# c200.net
KiCad netlist of a schematic drawn in EAGLE
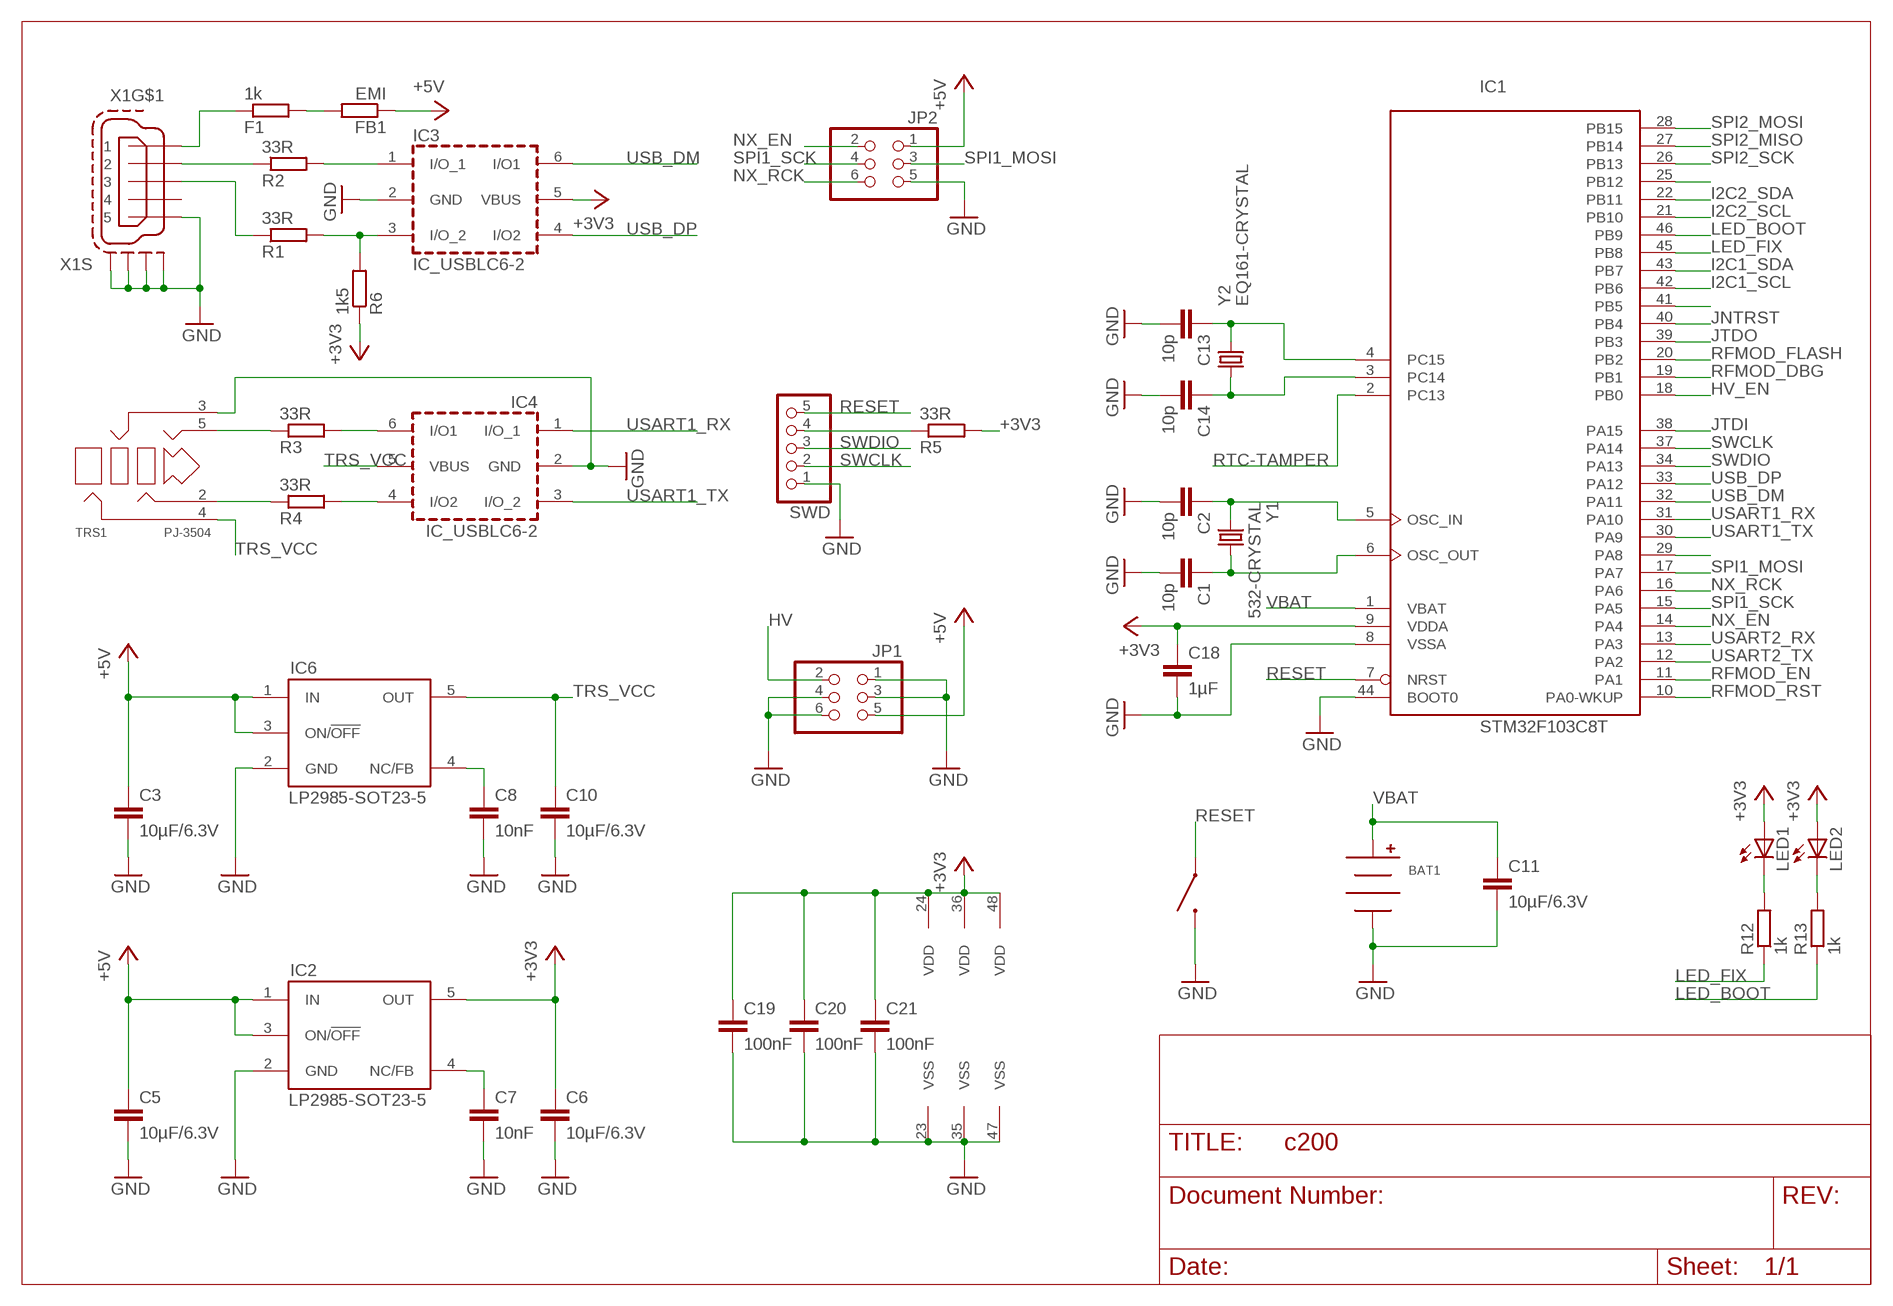
[diagram p0: schematic, sheet 1, part 1 of 2]
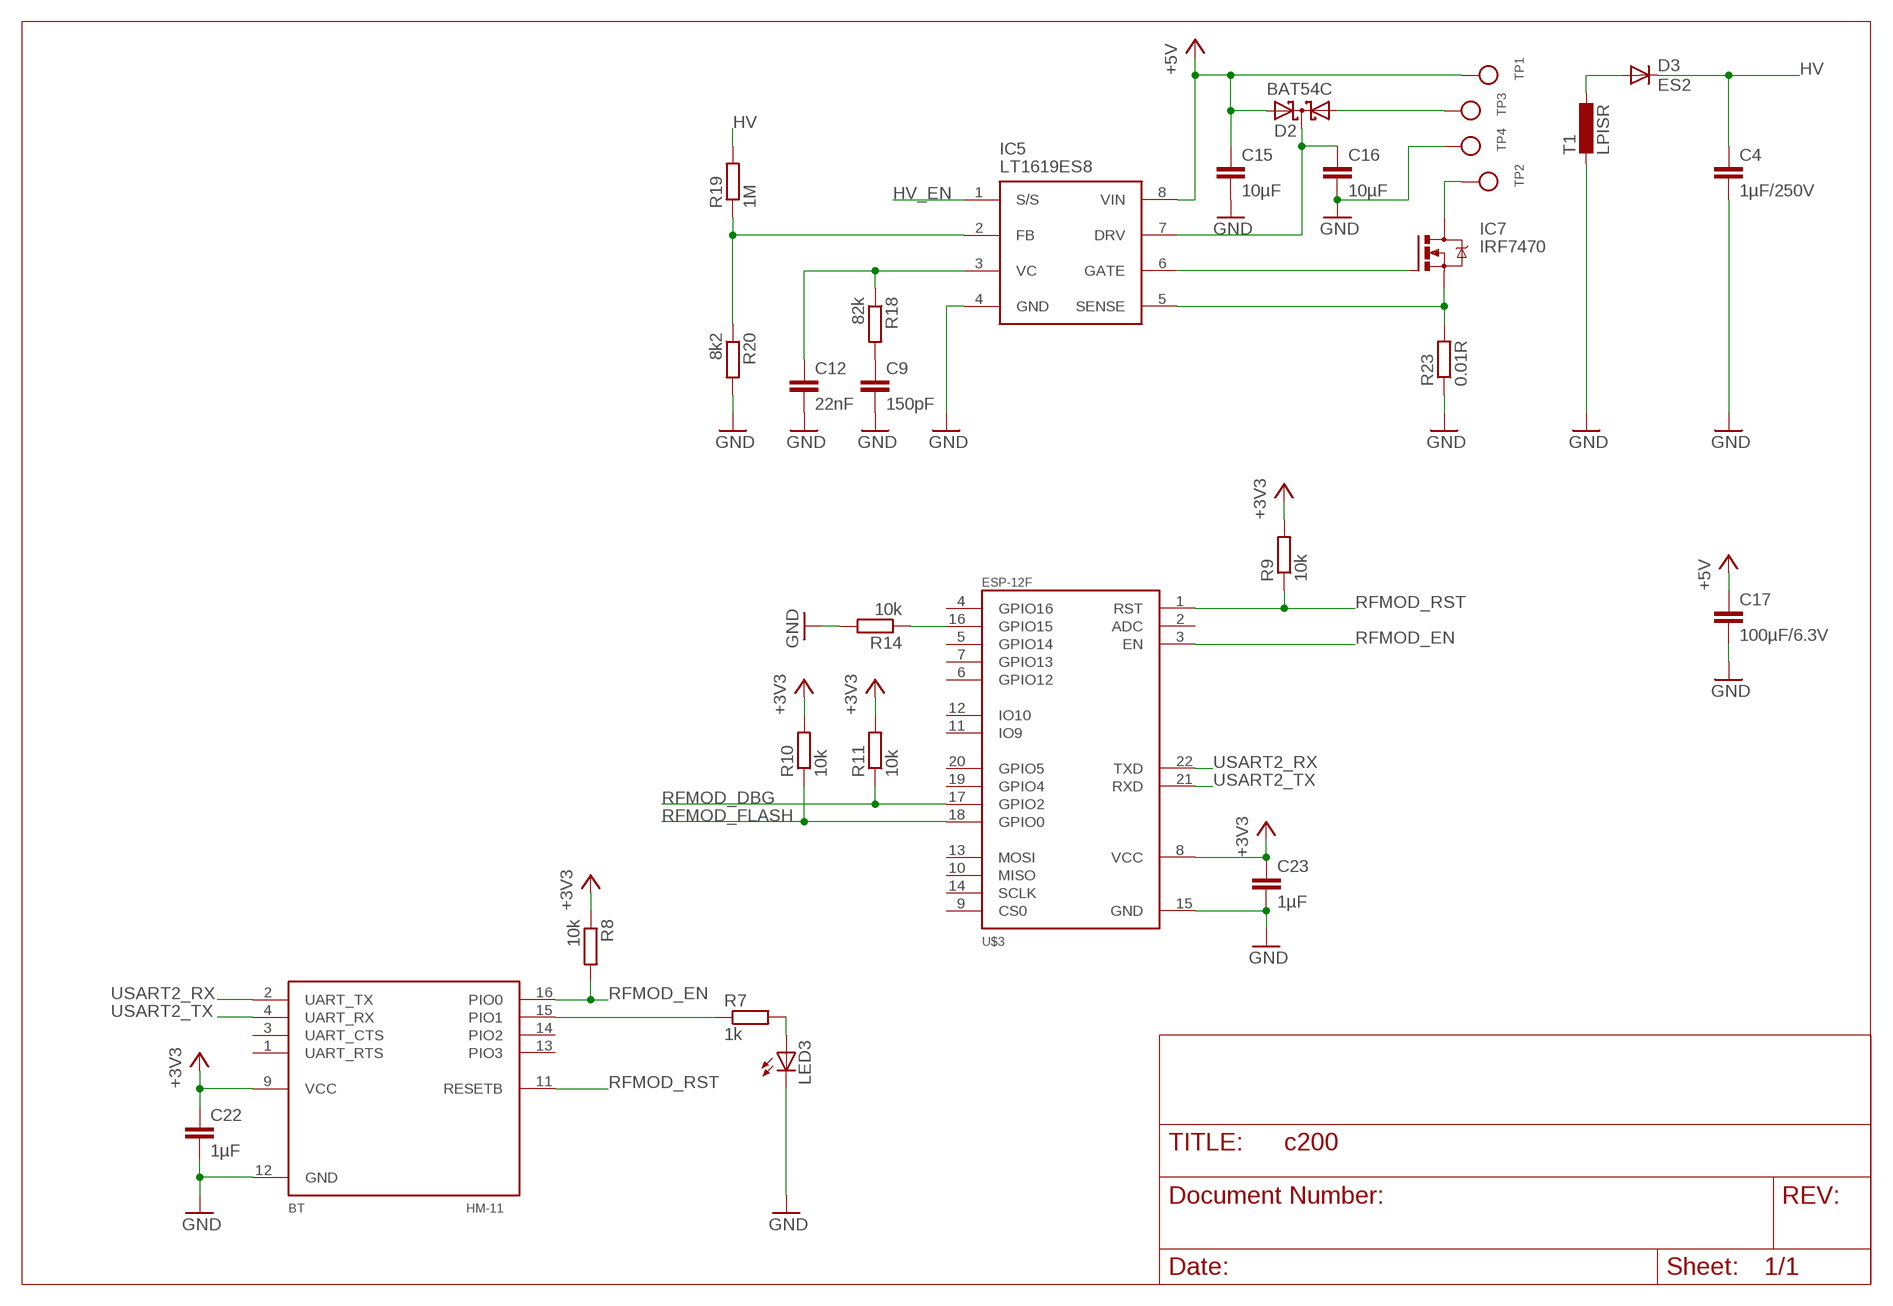
[diagram p1: schematic, sheet 1, part 2 of 2]

(export (version "E")
  (design (tool "Eeschema 10.0.6"))
  (components
    (comp (ref "BAT1")
      (value "CR1220-HOLDER")
      (footprint "eagle-import:HARWIN-CR1220")
      (libsource (lib "eagle-import") (part "CR1220-HOLDER"))
    )
    (comp (ref "BT")
      (value "HM-11")
      (footprint "eagle-import:HM-11")
      (libsource (lib "eagle-import") (part "HM-11"))
    )
    (comp (ref "C1")
      (value "10p")
      (footprint "eagle-import:C0603")
      (libsource (lib "eagle-import") (part "C-EUC0603"))
    )
    (comp (ref "C2")
      (value "10p")
      (footprint "eagle-import:C0603")
      (libsource (lib "eagle-import") (part "C-EUC0603"))
    )
    (comp (ref "C3")
      (value "10µF/6.3V")
      (footprint "eagle-import:C0603")
      (libsource (lib "eagle-import") (part "C-EUC0603"))
    )
    (comp (ref "C4")
      (value "1µF/250V")
      (footprint "eagle-import:C2220K")
      (libsource (lib "eagle-import") (part "C-EUC2220K"))
    )
    (comp (ref "C5")
      (value "10µF/6.3V")
      (footprint "eagle-import:C0603")
      (libsource (lib "eagle-import") (part "C-EUC0603"))
    )
    (comp (ref "C6")
      (value "10µF/6.3V")
      (footprint "eagle-import:C0603")
      (libsource (lib "eagle-import") (part "C-EUC0603"))
    )
    (comp (ref "C7")
      (value "10nF")
      (footprint "eagle-import:C0603")
      (libsource (lib "eagle-import") (part "C-EUC0603"))
    )
    (comp (ref "C8")
      (value "10nF")
      (footprint "eagle-import:C0603")
      (libsource (lib "eagle-import") (part "C-EUC0603"))
    )
    (comp (ref "C9")
      (value "150pF")
      (footprint "eagle-import:C0603")
      (libsource (lib "eagle-import") (part "C-EUC0603"))
    )
    (comp (ref "C10")
      (value "10µF/6.3V")
      (footprint "eagle-import:C0603")
      (libsource (lib "eagle-import") (part "C-EUC0603"))
    )
    (comp (ref "C11")
      (value "10µF/6.3V")
      (footprint "eagle-import:C0603")
      (libsource (lib "eagle-import") (part "C-EUC0603"))
    )
    (comp (ref "C12")
      (value "22nF")
      (footprint "eagle-import:C0603")
      (libsource (lib "eagle-import") (part "C-EUC0603"))
    )
    (comp (ref "C13")
      (value "10p")
      (footprint "eagle-import:C0603")
      (libsource (lib "eagle-import") (part "C-EUC0603"))
    )
    (comp (ref "C14")
      (value "10p")
      (footprint "eagle-import:C0603")
      (libsource (lib "eagle-import") (part "C-EUC0603"))
    )
    (comp (ref "C15")
      (value "10µF")
      (footprint "eagle-import:C0603")
      (libsource (lib "eagle-import") (part "C-EUC0603"))
    )
    (comp (ref "C16")
      (value "10µF")
      (footprint "eagle-import:C0603")
      (libsource (lib "eagle-import") (part "C-EUC0603"))
    )
    (comp (ref "C17")
      (value "100µF/6.3V")
      (footprint "eagle-import:C1210")
      (libsource (lib "eagle-import") (part "C-EUC1210"))
    )
    (comp (ref "C18")
      (value "1µF")
      (footprint "eagle-import:C0603")
      (libsource (lib "eagle-import") (part "C-EUC0603"))
    )
    (comp (ref "C19")
      (value "100nF")
      (footprint "eagle-import:C0603")
      (libsource (lib "eagle-import") (part "C-EUC0603"))
    )
    (comp (ref "C20")
      (value "100nF")
      (footprint "eagle-import:C0603")
      (libsource (lib "eagle-import") (part "C-EUC0603"))
    )
    (comp (ref "C21")
      (value "100nF")
      (footprint "eagle-import:C0603")
      (libsource (lib "eagle-import") (part "C-EUC0603"))
    )
    (comp (ref "C22")
      (value "1µF")
      (footprint "eagle-import:C0603")
      (libsource (lib "eagle-import") (part "C-EUC0603"))
    )
    (comp (ref "C23")
      (value "1µF")
      (footprint "eagle-import:C0603")
      (libsource (lib "eagle-import") (part "C-EUC0603"))
    )
    (comp (ref "D2")
      (value "BAT54C")
      (footprint "eagle-import:SOT23")
      (libsource (lib "eagle-import") (part "BAT54C"))
    )
    (comp (ref "D3")
      (value "ES2")
      (footprint "eagle-import:DO-214AA")
      (libsource (lib "eagle-import") (part "ES2"))
    )
    (comp (ref "F1")
      (value "1k")
      (footprint "eagle-import:R0603")
      (libsource (lib "eagle-import") (part "R-EU_R0603"))
    )
    (comp (ref "FB1")
      (value "EMI")
      (footprint "eagle-import:R0603")
      (libsource (lib "eagle-import") (part "R-EU_R0603"))
    )
    (comp (ref "IC1")
      (value "STM32F103C8T")
      (footprint "eagle-import:LQFP48")
      (libsource (lib "eagle-import") (part "STM32F103CT8"))
    )
    (comp (ref "IC2")
      (value "LP2985-SOT23-5")
      (footprint "eagle-import:SOT23-5")
      (libsource (lib "eagle-import") (part "LP2985-SOT23-5"))
    )
    (comp (ref "IC3")
      (value "IC_USBLC6-2")
      (footprint "eagle-import:SOT-23-6L")
      (libsource (lib "eagle-import") (part "IC_USBLC6-2"))
    )
    (comp (ref "IC4")
      (value "IC_USBLC6-2")
      (footprint "eagle-import:SOT-23-6L")
      (libsource (lib "eagle-import") (part "IC_USBLC6-2"))
    )
    (comp (ref "IC5")
      (value "LT1619ES8")
      (footprint "eagle-import:SO8")
      (libsource (lib "eagle-import") (part "LT1619ES8"))
    )
    (comp (ref "IC6")
      (value "LP2985-SOT23-5")
      (footprint "eagle-import:SOT23-5")
      (libsource (lib "eagle-import") (part "LP2985-SOT23-5"))
    )
    (comp (ref "IC7")
      (value "IRF7470")
      (footprint "eagle-import:SO8")
      (libsource (lib "eagle-import") (part "IRF7470"))
    )
    (comp (ref "ISP")
      (value "TACT-SWITCH-40-40")
      (footprint "eagle-import:40-40")
      (libsource (lib "eagle-import") (part "TACT-SWITCH-40-40"))
    )
    (comp (ref "JP1")
      (value "PINHD-2X3_2.54-SMD")
      (footprint "eagle-import:2X03SMD")
      (libsource (lib "eagle-import") (part "PINHD-2X3_2.54-SMD"))
    )
    (comp (ref "JP2")
      (value "PINHD-2X3_2.54-SMD")
      (footprint "eagle-import:2X03SMD")
      (libsource (lib "eagle-import") (part "PINHD-2X3_2.54-SMD"))
    )
    (comp (ref "LED1")
      (value "LEDCHIP-LED0603")
      (footprint "eagle-import:CHIP-LED0603")
      (libsource (lib "eagle-import") (part "LEDCHIP-LED0603"))
    )
    (comp (ref "LED2")
      (value "LEDCHIP-LED0603")
      (footprint "eagle-import:CHIP-LED0603")
      (libsource (lib "eagle-import") (part "LEDCHIP-LED0603"))
    )
    (comp (ref "LED3")
      (value "LEDCHIP-LED0603")
      (footprint "eagle-import:CHIP-LED0603")
      (libsource (lib "eagle-import") (part "LEDCHIP-LED0603"))
    )
    (comp (ref "R1")
      (value "33R")
      (footprint "eagle-import:R0603")
      (libsource (lib "eagle-import") (part "R-EU_R0603"))
    )
    (comp (ref "R2")
      (value "33R")
      (footprint "eagle-import:R0603")
      (libsource (lib "eagle-import") (part "R-EU_R0603"))
    )
    (comp (ref "R3")
      (value "33R")
      (footprint "eagle-import:R0603")
      (libsource (lib "eagle-import") (part "R-EU_R0603"))
    )
    (comp (ref "R4")
      (value "33R")
      (footprint "eagle-import:R0603")
      (libsource (lib "eagle-import") (part "R-EU_R0603"))
    )
    (comp (ref "R5")
      (value "33R")
      (footprint "eagle-import:R0603")
      (libsource (lib "eagle-import") (part "R-EU_R0603"))
    )
    (comp (ref "R6")
      (value "1k5")
      (footprint "eagle-import:R0603")
      (libsource (lib "eagle-import") (part "R-EU_R0603"))
    )
    (comp (ref "R7")
      (value "1k")
      (footprint "eagle-import:R0603")
      (libsource (lib "eagle-import") (part "R-EU_R0603"))
    )
    (comp (ref "R8")
      (value "10k")
      (footprint "eagle-import:R0603")
      (libsource (lib "eagle-import") (part "R-EU_R0603"))
    )
    (comp (ref "R9")
      (value "10k")
      (footprint "eagle-import:R0603")
      (libsource (lib "eagle-import") (part "R-EU_R0603"))
    )
    (comp (ref "R10")
      (value "10k")
      (footprint "eagle-import:R0603")
      (libsource (lib "eagle-import") (part "R-EU_R0603"))
    )
    (comp (ref "R11")
      (value "10k")
      (footprint "eagle-import:R0603")
      (libsource (lib "eagle-import") (part "R-EU_R0603"))
    )
    (comp (ref "R12")
      (value "1k")
      (footprint "eagle-import:R0603")
      (libsource (lib "eagle-import") (part "R-EU_R0603"))
    )
    (comp (ref "R13")
      (value "1k")
      (footprint "eagle-import:R0603")
      (libsource (lib "eagle-import") (part "R-EU_R0603"))
    )
    (comp (ref "R14")
      (value "10k")
      (footprint "eagle-import:R0603")
      (libsource (lib "eagle-import") (part "R-EU_R0603"))
    )
    (comp (ref "R18")
      (value "82k")
      (footprint "eagle-import:R0603")
      (libsource (lib "eagle-import") (part "R-EU_R0603"))
    )
    (comp (ref "R19")
      (value "1M")
      (footprint "eagle-import:M1206")
      (libsource (lib "eagle-import") (part "R-EU_M1206"))
    )
    (comp (ref "R20")
      (value "8k2")
      (footprint "eagle-import:R0603")
      (libsource (lib "eagle-import") (part "R-EU_R0603"))
    )
    (comp (ref "R23")
      (value "0.01R")
      (footprint "eagle-import:R1206")
      (libsource (lib "eagle-import") (part "R-EU_R1206"))
    )
    (comp (ref "SWD")
      (value "HEADER-1X5ROUND")
      (footprint "eagle-import:1X05_ROUND")
      (libsource (lib "eagle-import") (part "HEADER-1X5ROUND"))
    )
    (comp (ref "T1")
      (value "LPISR")
      (footprint "eagle-import:PISR")
      (libsource (lib "eagle-import") (part "LPISR"))
    )
    (comp (ref "TP1")
      (value "TESTPOINTROUND2MM")
      (footprint "eagle-import:TESTPOINT_ROUND_2MM")
      (libsource (lib "eagle-import") (part "TESTPOINTROUND2MM"))
    )
    (comp (ref "TP2")
      (value "TESTPOINTROUND2MM")
      (footprint "eagle-import:TESTPOINT_ROUND_2MM")
      (libsource (lib "eagle-import") (part "TESTPOINTROUND2MM"))
    )
    (comp (ref "TP3")
      (value "TESTPOINTROUND2MM")
      (footprint "eagle-import:TESTPOINT_ROUND_2MM")
      (libsource (lib "eagle-import") (part "TESTPOINTROUND2MM"))
    )
    (comp (ref "TP4")
      (value "TESTPOINTROUND2MM")
      (footprint "eagle-import:TESTPOINT_ROUND_2MM")
      (libsource (lib "eagle-import") (part "TESTPOINTROUND2MM"))
    )
    (comp (ref "TRS1")
      (value "PJ-3504")
      (footprint "eagle-import:YD-PJ-3504")
      (libsource (lib "eagle-import") (part "PJ-3504"))
    )
    (comp (ref "U$3")
      (value "ESP-12F")
      (footprint "eagle-import:ESP-12F")
      (libsource (lib "eagle-import") (part "ESP-12F"))
    )
    (comp (ref "X1")
      (value "MINI-USB-SCHIELD-32005-201")
      (footprint "eagle-import:32005-201")
      (libsource (lib "eagle-import") (part "MINI-USB-SCHIELD-32005-201"))
    )
    (comp (ref "Y1")
      (value "532-CRYSTAL")
      (footprint "eagle-import:2PIN50X32")
      (libsource (lib "eagle-import") (part "532-CRYSTAL"))
    )
    (comp (ref "Y2")
      (value "EQ161-CRYSTAL")
      (footprint "eagle-import:EQ161")
      (libsource (lib "eagle-import") (part "EQ161-CRYSTAL"))
    )
  )
  (nets
    (net (code "1") (name "+3V3") (class "Default")
      (node (ref "BT") (pin "9") (pinfunction "VCC_9") (pintype "bidirectional"))
      (node (ref "C18") (pin "1") (pinfunction "1_1") (pintype "passive"))
      (node (ref "C19") (pin "1") (pinfunction "1_1") (pintype "passive"))
      (node (ref "C20") (pin "1") (pinfunction "1_1") (pintype "passive"))
      (node (ref "C21") (pin "1") (pinfunction "1_1") (pintype "passive"))
      (node (ref "C22") (pin "1") (pinfunction "1_1") (pintype "passive"))
      (node (ref "C23") (pin "1") (pinfunction "1_1") (pintype "passive"))
      (node (ref "C6") (pin "1") (pinfunction "1_1") (pintype "passive"))
      (node (ref "IC1") (pin "24") (pinfunction "VDD_24") (pintype "power_in"))
      (node (ref "IC1") (pin "36") (pinfunction "VDD_36") (pintype "power_in"))
      (node (ref "IC1") (pin "48") (pinfunction "VDD_48") (pintype "power_in"))
      (node (ref "IC1") (pin "9") (pinfunction "VDDA_9") (pintype "power_in"))
      (node (ref "IC2") (pin "5") (pinfunction "OUT_5") (pintype "bidirectional"))
      (node (ref "IC3") (pin "5") (pinfunction "VBUS_5") (pintype "bidirectional"))
      (node (ref "LED1") (pin "A") (pinfunction "A_A") (pintype "passive"))
      (node (ref "LED2") (pin "A") (pinfunction "A_A") (pintype "passive"))
      (node (ref "R10") (pin "2") (pinfunction "2_2") (pintype "passive"))
      (node (ref "R11") (pin "2") (pinfunction "2_2") (pintype "passive"))
      (node (ref "R5") (pin "2") (pinfunction "2_2") (pintype "passive"))
      (node (ref "R6") (pin "1") (pinfunction "1_1") (pintype "passive"))
      (node (ref "R8") (pin "1") (pinfunction "1_1") (pintype "passive"))
      (node (ref "R9") (pin "2") (pinfunction "2_2") (pintype "passive"))
      (node (ref "U$3") (pin "8") (pinfunction "VCC_8") (pintype "bidirectional"))
    )
    (net (code "2") (name "+5V") (class "Default")
      (node (ref "C15") (pin "1") (pinfunction "1_1") (pintype "passive"))
      (node (ref "C17") (pin "1") (pinfunction "1_1") (pintype "passive"))
      (node (ref "C3") (pin "1") (pinfunction "1_1") (pintype "passive"))
      (node (ref "C5") (pin "1") (pinfunction "1_1") (pintype "passive"))
      (node (ref "D2") (pin "2") (pinfunction "A2_2") (pintype "passive"))
      (node (ref "FB1") (pin "1") (pinfunction "1_1") (pintype "passive"))
      (node (ref "IC2") (pin "1") (pinfunction "IN_1") (pintype "bidirectional"))
      (node (ref "IC2") (pin "3") (pinfunction "ON/~{OFF}_3") (pintype "bidirectional"))
      (node (ref "IC5") (pin "8") (pinfunction "VIN_8") (pintype "bidirectional"))
      (node (ref "IC6") (pin "1") (pinfunction "IN_1") (pintype "bidirectional"))
      (node (ref "IC6") (pin "3") (pinfunction "ON/~{OFF}_3") (pintype "bidirectional"))
      (node (ref "JP1") (pin "5") (pinfunction "5_5") (pintype "passive"))
      (node (ref "JP2") (pin "1") (pinfunction "1_1") (pintype "passive"))
      (node (ref "TP1") (pin "P$1") (pinfunction "P$1_P$1") (pintype "bidirectional"))
    )
    (net (code "3") (name "/HV") (class "Default")
      (node (ref "C4") (pin "1") (pinfunction "1_1") (pintype "passive"))
      (node (ref "D3") (pin "C") (pinfunction "C_C") (pintype "passive"))
      (node (ref "JP1") (pin "2") (pinfunction "2_2") (pintype "passive"))
      (node (ref "R19") (pin "2") (pinfunction "2_2") (pintype "passive"))
    )
    (net (code "4") (name "/HV_EN") (class "Default")
      (node (ref "IC1") (pin "18") (pinfunction "PB0_18") (pintype "bidirectional"))
      (node (ref "IC5") (pin "1") (pinfunction "S/S_1") (pintype "bidirectional"))
    )
    (net (code "5") (name "/I2C1_SCL") (class "Default")
      (node (ref "IC1") (pin "42") (pinfunction "PB6_42") (pintype "bidirectional"))
    )
    (net (code "6") (name "/I2C1_SDA") (class "Default")
      (node (ref "IC1") (pin "43") (pinfunction "PB7_43") (pintype "bidirectional"))
    )
    (net (code "7") (name "/I2C2_SCL") (class "Default")
      (node (ref "IC1") (pin "21") (pinfunction "PB10_21") (pintype "bidirectional"))
    )
    (net (code "8") (name "/I2C2_SDA") (class "Default")
      (node (ref "IC1") (pin "22") (pinfunction "PB11_22") (pintype "bidirectional"))
    )
    (net (code "9") (name "/JNTRST") (class "Default")
      (node (ref "IC1") (pin "40") (pinfunction "PB4_40") (pintype "bidirectional"))
    )
    (net (code "10") (name "/JTDI") (class "Default")
      (node (ref "IC1") (pin "38") (pinfunction "PA15_38") (pintype "bidirectional"))
    )
    (net (code "11") (name "/JTDO") (class "Default")
      (node (ref "IC1") (pin "39") (pinfunction "PB3_39") (pintype "bidirectional"))
    )
    (net (code "12") (name "/LED_BOOT") (class "Default")
      (node (ref "IC1") (pin "46") (pinfunction "PB9_46") (pintype "bidirectional"))
      (node (ref "R13") (pin "1") (pinfunction "1_1") (pintype "passive"))
    )
    (net (code "13") (name "/LED_FIX") (class "Default")
      (node (ref "IC1") (pin "45") (pinfunction "PB8_45") (pintype "bidirectional"))
      (node (ref "R12") (pin "1") (pinfunction "1_1") (pintype "passive"))
    )
    (net (code "14") (name "/NX_EN") (class "Default")
      (node (ref "IC1") (pin "14") (pinfunction "PA4_14") (pintype "bidirectional"))
      (node (ref "JP2") (pin "2") (pinfunction "2_2") (pintype "passive"))
    )
    (net (code "15") (name "/NX_RCK") (class "Default")
      (node (ref "IC1") (pin "16") (pinfunction "PA6_16") (pintype "bidirectional"))
      (node (ref "JP2") (pin "6") (pinfunction "6_6") (pintype "passive"))
    )
    (net (code "16") (name "/RESET") (class "Default")
      (node (ref "IC1") (pin "7") (pinfunction "NRST_7") (pintype "bidirectional"))
      (node (ref "ISP") (pin "3") (pinfunction "P$2_3") (pintype "bidirectional"))
      (node (ref "ISP") (pin "4") (pinfunction "P$2_4") (pintype "bidirectional"))
      (node (ref "SWD") (pin "5") (pinfunction "5_5") (pintype "passive"))
    )
    (net (code "17") (name "/RFMOD_DBG") (class "Default")
      (node (ref "IC1") (pin "19") (pinfunction "PB1_19") (pintype "bidirectional"))
      (node (ref "R11") (pin "1") (pinfunction "1_1") (pintype "passive"))
      (node (ref "U$3") (pin "17") (pinfunction "GPIO2_17") (pintype "bidirectional"))
    )
    (net (code "18") (name "/RFMOD_EN") (class "Default")
      (node (ref "BT") (pin "16") (pinfunction "PIO0_16") (pintype "bidirectional"))
      (node (ref "IC1") (pin "11") (pinfunction "PA1_11") (pintype "bidirectional"))
      (node (ref "R8") (pin "2") (pinfunction "2_2") (pintype "passive"))
      (node (ref "U$3") (pin "3") (pinfunction "EN_3") (pintype "bidirectional"))
    )
    (net (code "19") (name "/RFMOD_FLASH") (class "Default")
      (node (ref "IC1") (pin "20") (pinfunction "PB2_20") (pintype "bidirectional"))
      (node (ref "R10") (pin "1") (pinfunction "1_1") (pintype "passive"))
      (node (ref "U$3") (pin "18") (pinfunction "GPIO0_18") (pintype "bidirectional"))
    )
    (net (code "20") (name "/RFMOD_RST") (class "Default")
      (node (ref "BT") (pin "11") (pinfunction "RESETB_11") (pintype "bidirectional"))
      (node (ref "IC1") (pin "10") (pinfunction "PA0-WKUP_10") (pintype "bidirectional"))
      (node (ref "R9") (pin "1") (pinfunction "1_1") (pintype "passive"))
      (node (ref "U$3") (pin "1") (pinfunction "RST_1") (pintype "bidirectional"))
    )
    (net (code "21") (name "/RTC-TAMPER") (class "Default")
      (node (ref "IC1") (pin "2") (pinfunction "PC13_2") (pintype "bidirectional"))
    )
    (net (code "22") (name "/SPI1_MOSI") (class "Default")
      (node (ref "IC1") (pin "17") (pinfunction "PA7_17") (pintype "bidirectional"))
      (node (ref "JP2") (pin "3") (pinfunction "3_3") (pintype "passive"))
    )
    (net (code "23") (name "/SPI1_SCK") (class "Default")
      (node (ref "IC1") (pin "15") (pinfunction "PA5_15") (pintype "bidirectional"))
      (node (ref "JP2") (pin "4") (pinfunction "4_4") (pintype "passive"))
    )
    (net (code "24") (name "/SPI2_MISO") (class "Default")
      (node (ref "IC1") (pin "27") (pinfunction "PB14_27") (pintype "bidirectional"))
    )
    (net (code "25") (name "/SPI2_MOSI") (class "Default")
      (node (ref "IC1") (pin "28") (pinfunction "PB15_28") (pintype "bidirectional"))
    )
    (net (code "26") (name "/SPI2_SCK") (class "Default")
      (node (ref "IC1") (pin "26") (pinfunction "PB13_26") (pintype "bidirectional"))
    )
    (net (code "27") (name "/SWCLK") (class "Default")
      (node (ref "IC1") (pin "37") (pinfunction "PA14_37") (pintype "bidirectional"))
      (node (ref "SWD") (pin "2") (pinfunction "2_2") (pintype "passive"))
    )
    (net (code "28") (name "/SWDIO") (class "Default")
      (node (ref "IC1") (pin "34") (pinfunction "PA13_34") (pintype "bidirectional"))
      (node (ref "SWD") (pin "3") (pinfunction "3_3") (pintype "passive"))
    )
    (net (code "29") (name "/TRS_VCC") (class "Default")
      (node (ref "C10") (pin "1") (pinfunction "1_1") (pintype "passive"))
      (node (ref "IC4") (pin "5") (pinfunction "VBUS_5") (pintype "bidirectional"))
      (node (ref "IC6") (pin "5") (pinfunction "OUT_5") (pintype "bidirectional"))
      (node (ref "TRS1") (pin "4") (pinfunction "4_4") (pintype "bidirectional"))
    )
    (net (code "30") (name "/USART1_RX") (class "Default")
      (node (ref "IC1") (pin "31") (pinfunction "PA10_31") (pintype "bidirectional"))
      (node (ref "IC4") (pin "1") (pinfunction "I/O_1_1") (pintype "bidirectional"))
    )
    (net (code "31") (name "/USART1_TX") (class "Default")
      (node (ref "IC1") (pin "30") (pinfunction "PA9_30") (pintype "bidirectional"))
      (node (ref "IC4") (pin "3") (pinfunction "I/O_2_3") (pintype "bidirectional"))
    )
    (net (code "32") (name "/USART2_RX") (class "Default")
      (node (ref "BT") (pin "2") (pinfunction "UART_TX_2") (pintype "bidirectional"))
      (node (ref "IC1") (pin "13") (pinfunction "PA3_13") (pintype "bidirectional"))
      (node (ref "U$3") (pin "22") (pinfunction "TXD_22") (pintype "bidirectional"))
    )
    (net (code "33") (name "/USART2_TX") (class "Default")
      (node (ref "BT") (pin "4") (pinfunction "UART_RX_4") (pintype "bidirectional"))
      (node (ref "IC1") (pin "12") (pinfunction "PA2_12") (pintype "bidirectional"))
      (node (ref "U$3") (pin "21") (pinfunction "RXD_21") (pintype "bidirectional"))
    )
    (net (code "34") (name "/USB_DM") (class "Default")
      (node (ref "IC1") (pin "32") (pinfunction "PA11_32") (pintype "bidirectional"))
      (node (ref "IC3") (pin "6") (pinfunction "I/O1_6") (pintype "bidirectional"))
    )
    (net (code "35") (name "/USB_DP") (class "Default")
      (node (ref "IC1") (pin "33") (pinfunction "PA12_33") (pintype "bidirectional"))
      (node (ref "IC3") (pin "4") (pinfunction "I/O2_4") (pintype "bidirectional"))
    )
    (net (code "36") (name "/VBAT") (class "Default")
      (node (ref "BAT1") (pin "POS") (pinfunction "POS_POS") (pintype "bidirectional"))
      (node (ref "C11") (pin "1") (pinfunction "1_1") (pintype "passive"))
      (node (ref "IC1") (pin "1") (pinfunction "VBAT_1") (pintype "power_in"))
    )
    (net (code "37") (name "GND") (class "Default")
      (node (ref "BAT1") (pin "NEG") (pinfunction "NEG_NEG") (pintype "bidirectional"))
      (node (ref "BT") (pin "12") (pinfunction "GND_12") (pintype "bidirectional"))
      (node (ref "C1") (pin "2") (pinfunction "2_2") (pintype "passive"))
      (node (ref "C10") (pin "2") (pinfunction "2_2") (pintype "passive"))
      (node (ref "C11") (pin "2") (pinfunction "2_2") (pintype "passive"))
      (node (ref "C12") (pin "2") (pinfunction "2_2") (pintype "passive"))
      (node (ref "C13") (pin "2") (pinfunction "2_2") (pintype "passive"))
      (node (ref "C14") (pin "2") (pinfunction "2_2") (pintype "passive"))
      (node (ref "C15") (pin "2") (pinfunction "2_2") (pintype "passive"))
      (node (ref "C16") (pin "2") (pinfunction "2_2") (pintype "passive"))
      (node (ref "C17") (pin "2") (pinfunction "2_2") (pintype "passive"))
      (node (ref "C18") (pin "2") (pinfunction "2_2") (pintype "passive"))
      (node (ref "C19") (pin "2") (pinfunction "2_2") (pintype "passive"))
      (node (ref "C2") (pin "2") (pinfunction "2_2") (pintype "passive"))
      (node (ref "C20") (pin "2") (pinfunction "2_2") (pintype "passive"))
      (node (ref "C21") (pin "2") (pinfunction "2_2") (pintype "passive"))
      (node (ref "C22") (pin "2") (pinfunction "2_2") (pintype "passive"))
      (node (ref "C23") (pin "2") (pinfunction "2_2") (pintype "passive"))
      (node (ref "C3") (pin "2") (pinfunction "2_2") (pintype "passive"))
      (node (ref "C4") (pin "2") (pinfunction "2_2") (pintype "passive"))
      (node (ref "C5") (pin "2") (pinfunction "2_2") (pintype "passive"))
      (node (ref "C6") (pin "2") (pinfunction "2_2") (pintype "passive"))
      (node (ref "C7") (pin "2") (pinfunction "2_2") (pintype "passive"))
      (node (ref "C8") (pin "2") (pinfunction "2_2") (pintype "passive"))
      (node (ref "C9") (pin "2") (pinfunction "2_2") (pintype "passive"))
      (node (ref "IC1") (pin "23") (pinfunction "VSS_23") (pintype "power_in"))
      (node (ref "IC1") (pin "35") (pinfunction "VSS_35") (pintype "power_in"))
      (node (ref "IC1") (pin "44") (pinfunction "BOOT0_44") (pintype "input"))
      (node (ref "IC1") (pin "47") (pinfunction "VSS_47") (pintype "power_in"))
      (node (ref "IC1") (pin "8") (pinfunction "VSSA_8") (pintype "power_in"))
      (node (ref "IC2") (pin "2") (pinfunction "GND_2") (pintype "bidirectional"))
      (node (ref "IC3") (pin "2") (pinfunction "GND_2") (pintype "bidirectional"))
      (node (ref "IC4") (pin "2") (pinfunction "GND_2") (pintype "bidirectional"))
      (node (ref "IC5") (pin "4") (pinfunction "GND_4") (pintype "bidirectional"))
      (node (ref "IC6") (pin "2") (pinfunction "GND_2") (pintype "bidirectional"))
      (node (ref "ISP") (pin "1") (pinfunction "P$1_1") (pintype "bidirectional"))
      (node (ref "ISP") (pin "2") (pinfunction "P$1_2") (pintype "bidirectional"))
      (node (ref "JP1") (pin "1") (pinfunction "1_1") (pintype "passive"))
      (node (ref "JP1") (pin "3") (pinfunction "3_3") (pintype "passive"))
      (node (ref "JP1") (pin "4") (pinfunction "4_4") (pintype "passive"))
      (node (ref "JP1") (pin "6") (pinfunction "6_6") (pintype "passive"))
      (node (ref "JP2") (pin "5") (pinfunction "5_5") (pintype "passive"))
      (node (ref "LED3") (pin "C") (pinfunction "C_C") (pintype "passive"))
      (node (ref "R14") (pin "2") (pinfunction "2_2") (pintype "passive"))
      (node (ref "R20") (pin "2") (pinfunction "2_2") (pintype "passive"))
      (node (ref "R23") (pin "1") (pinfunction "1_1") (pintype "passive"))
      (node (ref "SWD") (pin "1") (pinfunction "1_1") (pintype "passive"))
      (node (ref "T1") (pin "P$2") (pinfunction "2_P$2") (pintype "passive"))
      (node (ref "TP4") (pin "P$1") (pinfunction "P$1_P$1") (pintype "bidirectional"))
      (node (ref "TRS1") (pin "3") (pinfunction "3_3") (pintype "bidirectional"))
      (node (ref "U$3") (pin "15") (pinfunction "GND_15") (pintype "bidirectional"))
      (node (ref "X1") (pin "5") (pinfunction "5_5") (pintype "passive"))
      (node (ref "X1") (pin "M1") (pinfunction "S1_M1") (pintype "passive"))
      (node (ref "X1") (pin "M2") (pinfunction "S2_M2") (pintype "passive"))
      (node (ref "X1") (pin "M3") (pinfunction "S3_M3") (pintype "passive"))
      (node (ref "X1") (pin "M4") (pinfunction "S4_M4") (pintype "passive"))
    )
    (net (code "38") (name "Net-(BT-PIO1)") (class "Default")
      (node (ref "BT") (pin "15") (pinfunction "PIO1_15") (pintype "bidirectional"))
      (node (ref "R7") (pin "1") (pinfunction "1_1") (pintype "passive"))
    )
    (net (code "39") (name "Net-(C9-Pad1)") (class "Default")
      (node (ref "C9") (pin "1") (pinfunction "1_1") (pintype "passive"))
      (node (ref "R18") (pin "2") (pinfunction "2_2") (pintype "passive"))
    )
    (net (code "40") (name "Net-(D2-A1)") (class "Default")
      (node (ref "D2") (pin "1") (pinfunction "A1_1") (pintype "passive"))
      (node (ref "TP3") (pin "P$1") (pinfunction "P$1_P$1") (pintype "bidirectional"))
    )
    (net (code "41") (name "Net-(D2-CC)") (class "Default")
      (node (ref "C16") (pin "1") (pinfunction "1_1") (pintype "passive"))
      (node (ref "D2") (pin "3") (pinfunction "CC_3") (pintype "passive"))
      (node (ref "IC5") (pin "7") (pinfunction "DRV_7") (pintype "bidirectional"))
    )
    (net (code "42") (name "Net-(F1-Pad1)") (class "Default")
      (node (ref "F1") (pin "1") (pinfunction "1_1") (pintype "passive"))
      (node (ref "X1") (pin "1") (pinfunction "1_1") (pintype "passive"))
    )
    (net (code "43") (name "Net-(F1-Pad2)") (class "Default")
      (node (ref "F1") (pin "2") (pinfunction "2_2") (pintype "passive"))
      (node (ref "FB1") (pin "2") (pinfunction "2_2") (pintype "passive"))
    )
    (net (code "44") (name "Net-(IC1A-OSC_IN)") (class "Default")
      (node (ref "C2") (pin "1") (pinfunction "1_1") (pintype "passive"))
      (node (ref "IC1") (pin "5") (pinfunction "OSC_IN_5") (pintype "bidirectional"))
      (node (ref "Y1") (pin "P$2") (pinfunction "2_P$2") (pintype "passive"))
    )
    (net (code "45") (name "Net-(IC1A-OSC_OUT)") (class "Default")
      (node (ref "C1") (pin "1") (pinfunction "1_1") (pintype "passive"))
      (node (ref "IC1") (pin "6") (pinfunction "OSC_OUT_6") (pintype "bidirectional"))
      (node (ref "Y1") (pin "P$1") (pinfunction "1_P$1") (pintype "passive"))
    )
    (net (code "46") (name "Net-(IC1A-PC14)") (class "Default")
      (node (ref "C14") (pin "1") (pinfunction "1_1") (pintype "passive"))
      (node (ref "IC1") (pin "3") (pinfunction "PC14_3") (pintype "bidirectional"))
      (node (ref "Y2") (pin "P$2") (pinfunction "2_P$2") (pintype "passive"))
    )
    (net (code "47") (name "Net-(IC1A-PC15)") (class "Default")
      (node (ref "C13") (pin "1") (pinfunction "1_1") (pintype "passive"))
      (node (ref "IC1") (pin "4") (pinfunction "PC15_4") (pintype "bidirectional"))
      (node (ref "Y2") (pin "P$1") (pinfunction "1_P$1") (pintype "passive"))
    )
    (net (code "48") (name "Net-(IC2-NC{slash}FB)") (class "Default")
      (node (ref "C7") (pin "1") (pinfunction "1_1") (pintype "passive"))
      (node (ref "IC2") (pin "4") (pinfunction "NC/FB_4") (pintype "bidirectional"))
    )
    (net (code "49") (name "Net-(IC3-I{slash}O_1)") (class "Default")
      (node (ref "IC3") (pin "1") (pinfunction "I/O_1_1") (pintype "bidirectional"))
      (node (ref "R2") (pin "2") (pinfunction "2_2") (pintype "passive"))
    )
    (net (code "50") (name "Net-(IC3-I{slash}O_2)") (class "Default")
      (node (ref "IC3") (pin "3") (pinfunction "I/O_2_3") (pintype "bidirectional"))
      (node (ref "R1") (pin "2") (pinfunction "2_2") (pintype "passive"))
      (node (ref "R6") (pin "2") (pinfunction "2_2") (pintype "passive"))
    )
    (net (code "51") (name "Net-(IC4-I{slash}O1)") (class "Default")
      (node (ref "IC4") (pin "6") (pinfunction "I/O1_6") (pintype "bidirectional"))
      (node (ref "R3") (pin "2") (pinfunction "2_2") (pintype "passive"))
    )
    (net (code "52") (name "Net-(IC4-I{slash}O2)") (class "Default")
      (node (ref "IC4") (pin "4") (pinfunction "I/O2_4") (pintype "bidirectional"))
      (node (ref "R4") (pin "2") (pinfunction "2_2") (pintype "passive"))
    )
    (net (code "53") (name "Net-(IC5-FB)") (class "Default")
      (node (ref "IC5") (pin "2") (pinfunction "FB_2") (pintype "bidirectional"))
      (node (ref "R19") (pin "1") (pinfunction "1_1") (pintype "passive"))
      (node (ref "R20") (pin "1") (pinfunction "1_1") (pintype "passive"))
    )
    (net (code "54") (name "Net-(IC5-GATE)") (class "Default")
      (node (ref "IC5") (pin "6") (pinfunction "GATE_6") (pintype "bidirectional"))
      (node (ref "IC7") (pin "4") (pinfunction "G_4") (pintype "passive"))
    )
    (net (code "55") (name "Net-(IC5-SENSE)") (class "Default")
      (node (ref "IC5") (pin "5") (pinfunction "SENSE_5") (pintype "bidirectional"))
      (node (ref "IC7") (pin "1") (pinfunction "S_1") (pintype "passive"))
      (node (ref "IC7") (pin "2") (pinfunction "S_2") (pintype "passive"))
      (node (ref "IC7") (pin "3") (pinfunction "S_3") (pintype "passive"))
      (node (ref "R23") (pin "2") (pinfunction "2_2") (pintype "passive"))
    )
    (net (code "56") (name "Net-(IC5-VC)") (class "Default")
      (node (ref "C12") (pin "1") (pinfunction "1_1") (pintype "passive"))
      (node (ref "IC5") (pin "3") (pinfunction "VC_3") (pintype "bidirectional"))
      (node (ref "R18") (pin "1") (pinfunction "1_1") (pintype "passive"))
    )
    (net (code "57") (name "Net-(IC6-NC{slash}FB)") (class "Default")
      (node (ref "C8") (pin "1") (pinfunction "1_1") (pintype "passive"))
      (node (ref "IC6") (pin "4") (pinfunction "NC/FB_4") (pintype "bidirectional"))
    )
    (net (code "58") (name "Net-(IC7-D-Pad5)") (class "Default")
      (node (ref "IC7") (pin "5") (pinfunction "D_5") (pintype "passive"))
      (node (ref "IC7") (pin "6") (pinfunction "D_6") (pintype "passive"))
      (node (ref "IC7") (pin "7") (pinfunction "D_7") (pintype "passive"))
      (node (ref "IC7") (pin "8") (pinfunction "D_8") (pintype "passive"))
      (node (ref "TP2") (pin "P$1") (pinfunction "P$1_P$1") (pintype "bidirectional"))
    )
    (net (code "59") (name "Net-(LED1-PadC)") (class "Default")
      (node (ref "LED1") (pin "C") (pinfunction "C_C") (pintype "passive"))
      (node (ref "R12") (pin "2") (pinfunction "2_2") (pintype "passive"))
    )
    (net (code "60") (name "Net-(LED2-PadC)") (class "Default")
      (node (ref "LED2") (pin "C") (pinfunction "C_C") (pintype "passive"))
      (node (ref "R13") (pin "2") (pinfunction "2_2") (pintype "passive"))
    )
    (net (code "61") (name "Net-(LED3-PadA)") (class "Default")
      (node (ref "LED3") (pin "A") (pinfunction "A_A") (pintype "passive"))
      (node (ref "R7") (pin "2") (pinfunction "2_2") (pintype "passive"))
    )
    (net (code "62") (name "Net-(R1-Pad1)") (class "Default")
      (node (ref "R1") (pin "1") (pinfunction "1_1") (pintype "passive"))
      (node (ref "X1") (pin "3") (pinfunction "3_3") (pintype "passive"))
    )
    (net (code "63") (name "Net-(R2-Pad1)") (class "Default")
      (node (ref "R2") (pin "1") (pinfunction "1_1") (pintype "passive"))
      (node (ref "X1") (pin "2") (pinfunction "2_2") (pintype "passive"))
    )
    (net (code "64") (name "Net-(R3-Pad1)") (class "Default")
      (node (ref "R3") (pin "1") (pinfunction "1_1") (pintype "passive"))
      (node (ref "TRS1") (pin "5") (pinfunction "5_5") (pintype "bidirectional"))
    )
    (net (code "65") (name "Net-(R4-Pad1)") (class "Default")
      (node (ref "R4") (pin "1") (pinfunction "1_1") (pintype "passive"))
      (node (ref "TRS1") (pin "2") (pinfunction "2_2") (pintype "bidirectional"))
    )
    (net (code "66") (name "Net-(R5-Pad1)") (class "Default")
      (node (ref "R5") (pin "1") (pinfunction "1_1") (pintype "passive"))
      (node (ref "SWD") (pin "4") (pinfunction "4_4") (pintype "passive"))
    )
    (net (code "67") (name "Net-(T1-1)") (class "Default")
      (node (ref "D3") (pin "A") (pinfunction "A_A") (pintype "passive"))
      (node (ref "T1") (pin "P$1") (pinfunction "1_P$1") (pintype "passive"))
    )
    (net (code "68") (name "Net-(U$3-GPIO15)") (class "Default")
      (node (ref "R14") (pin "1") (pinfunction "1_1") (pintype "passive"))
      (node (ref "U$3") (pin "16") (pinfunction "GPIO15_16") (pintype "bidirectional"))
    )
    (net (code "69") (name "unconnected-(BT-PIO2-Pad14)") (class "Default")
      (node (ref "BT") (pin "14") (pinfunction "PIO2_14") (pintype "bidirectional"))
    )
    (net (code "70") (name "unconnected-(BT-PIO3-Pad13)") (class "Default")
      (node (ref "BT") (pin "13") (pinfunction "PIO3_13") (pintype "bidirectional"))
    )
    (net (code "71") (name "unconnected-(BT-UART_CTS-Pad3)") (class "Default")
      (node (ref "BT") (pin "3") (pinfunction "UART_CTS_3") (pintype "bidirectional"))
    )
    (net (code "72") (name "unconnected-(BT-UART_RTS-Pad1)") (class "Default")
      (node (ref "BT") (pin "1") (pinfunction "UART_RTS_1") (pintype "bidirectional"))
    )
    (net (code "73") (name "unconnected-(IC1A-PA8-Pad29)") (class "Default")
      (node (ref "IC1") (pin "29") (pinfunction "PA8_29") (pintype "bidirectional"))
    )
    (net (code "74") (name "unconnected-(IC1A-PB5-Pad41)") (class "Default")
      (node (ref "IC1") (pin "41") (pinfunction "PB5_41") (pintype "bidirectional"))
    )
    (net (code "75") (name "unconnected-(IC1A-PB12-Pad25)") (class "Default")
      (node (ref "IC1") (pin "25") (pinfunction "PB12_25") (pintype "bidirectional"))
    )
    (net (code "76") (name "unconnected-(U$3-ADC-Pad2)") (class "Default")
      (node (ref "U$3") (pin "2") (pinfunction "ADC_2") (pintype "bidirectional"))
    )
    (net (code "77") (name "unconnected-(U$3-CS0-Pad9)") (class "Default")
      (node (ref "U$3") (pin "9") (pinfunction "CS0_9") (pintype "bidirectional"))
    )
    (net (code "78") (name "unconnected-(U$3-GPIO4-Pad19)") (class "Default")
      (node (ref "U$3") (pin "19") (pinfunction "GPIO4_19") (pintype "bidirectional"))
    )
    (net (code "79") (name "unconnected-(U$3-GPIO5-Pad20)") (class "Default")
      (node (ref "U$3") (pin "20") (pinfunction "GPIO5_20") (pintype "bidirectional"))
    )
    (net (code "80") (name "unconnected-(U$3-GPIO12-Pad6)") (class "Default")
      (node (ref "U$3") (pin "6") (pinfunction "GPIO12_6") (pintype "bidirectional"))
    )
    (net (code "81") (name "unconnected-(U$3-GPIO13-Pad7)") (class "Default")
      (node (ref "U$3") (pin "7") (pinfunction "GPIO13_7") (pintype "bidirectional"))
    )
    (net (code "82") (name "unconnected-(U$3-GPIO14-Pad5)") (class "Default")
      (node (ref "U$3") (pin "5") (pinfunction "GPIO14_5") (pintype "bidirectional"))
    )
    (net (code "83") (name "unconnected-(U$3-GPIO16-Pad4)") (class "Default")
      (node (ref "U$3") (pin "4") (pinfunction "GPIO16_4") (pintype "bidirectional"))
    )
    (net (code "84") (name "unconnected-(U$3-IO9-Pad11)") (class "Default")
      (node (ref "U$3") (pin "11") (pinfunction "IO9_11") (pintype "bidirectional"))
    )
    (net (code "85") (name "unconnected-(U$3-IO10-Pad12)") (class "Default")
      (node (ref "U$3") (pin "12") (pinfunction "IO10_12") (pintype "bidirectional"))
    )
    (net (code "86") (name "unconnected-(U$3-MISO-Pad10)") (class "Default")
      (node (ref "U$3") (pin "10") (pinfunction "MISO_10") (pintype "bidirectional"))
    )
    (net (code "87") (name "unconnected-(U$3-MOSI-Pad13)") (class "Default")
      (node (ref "U$3") (pin "13") (pinfunction "MOSI_13") (pintype "bidirectional"))
    )
    (net (code "88") (name "unconnected-(U$3-SCLK-Pad14)") (class "Default")
      (node (ref "U$3") (pin "14") (pinfunction "SCLK_14") (pintype "bidirectional"))
    )
    (net (code "89") (name "unconnected-(X1-Pad4)") (class "Default")
      (node (ref "X1") (pin "4") (pinfunction "4_4") (pintype "passive"))
    )
  )
)
